# Mainboard.net
KiCad netlist of a schematic drawn in EAGLE
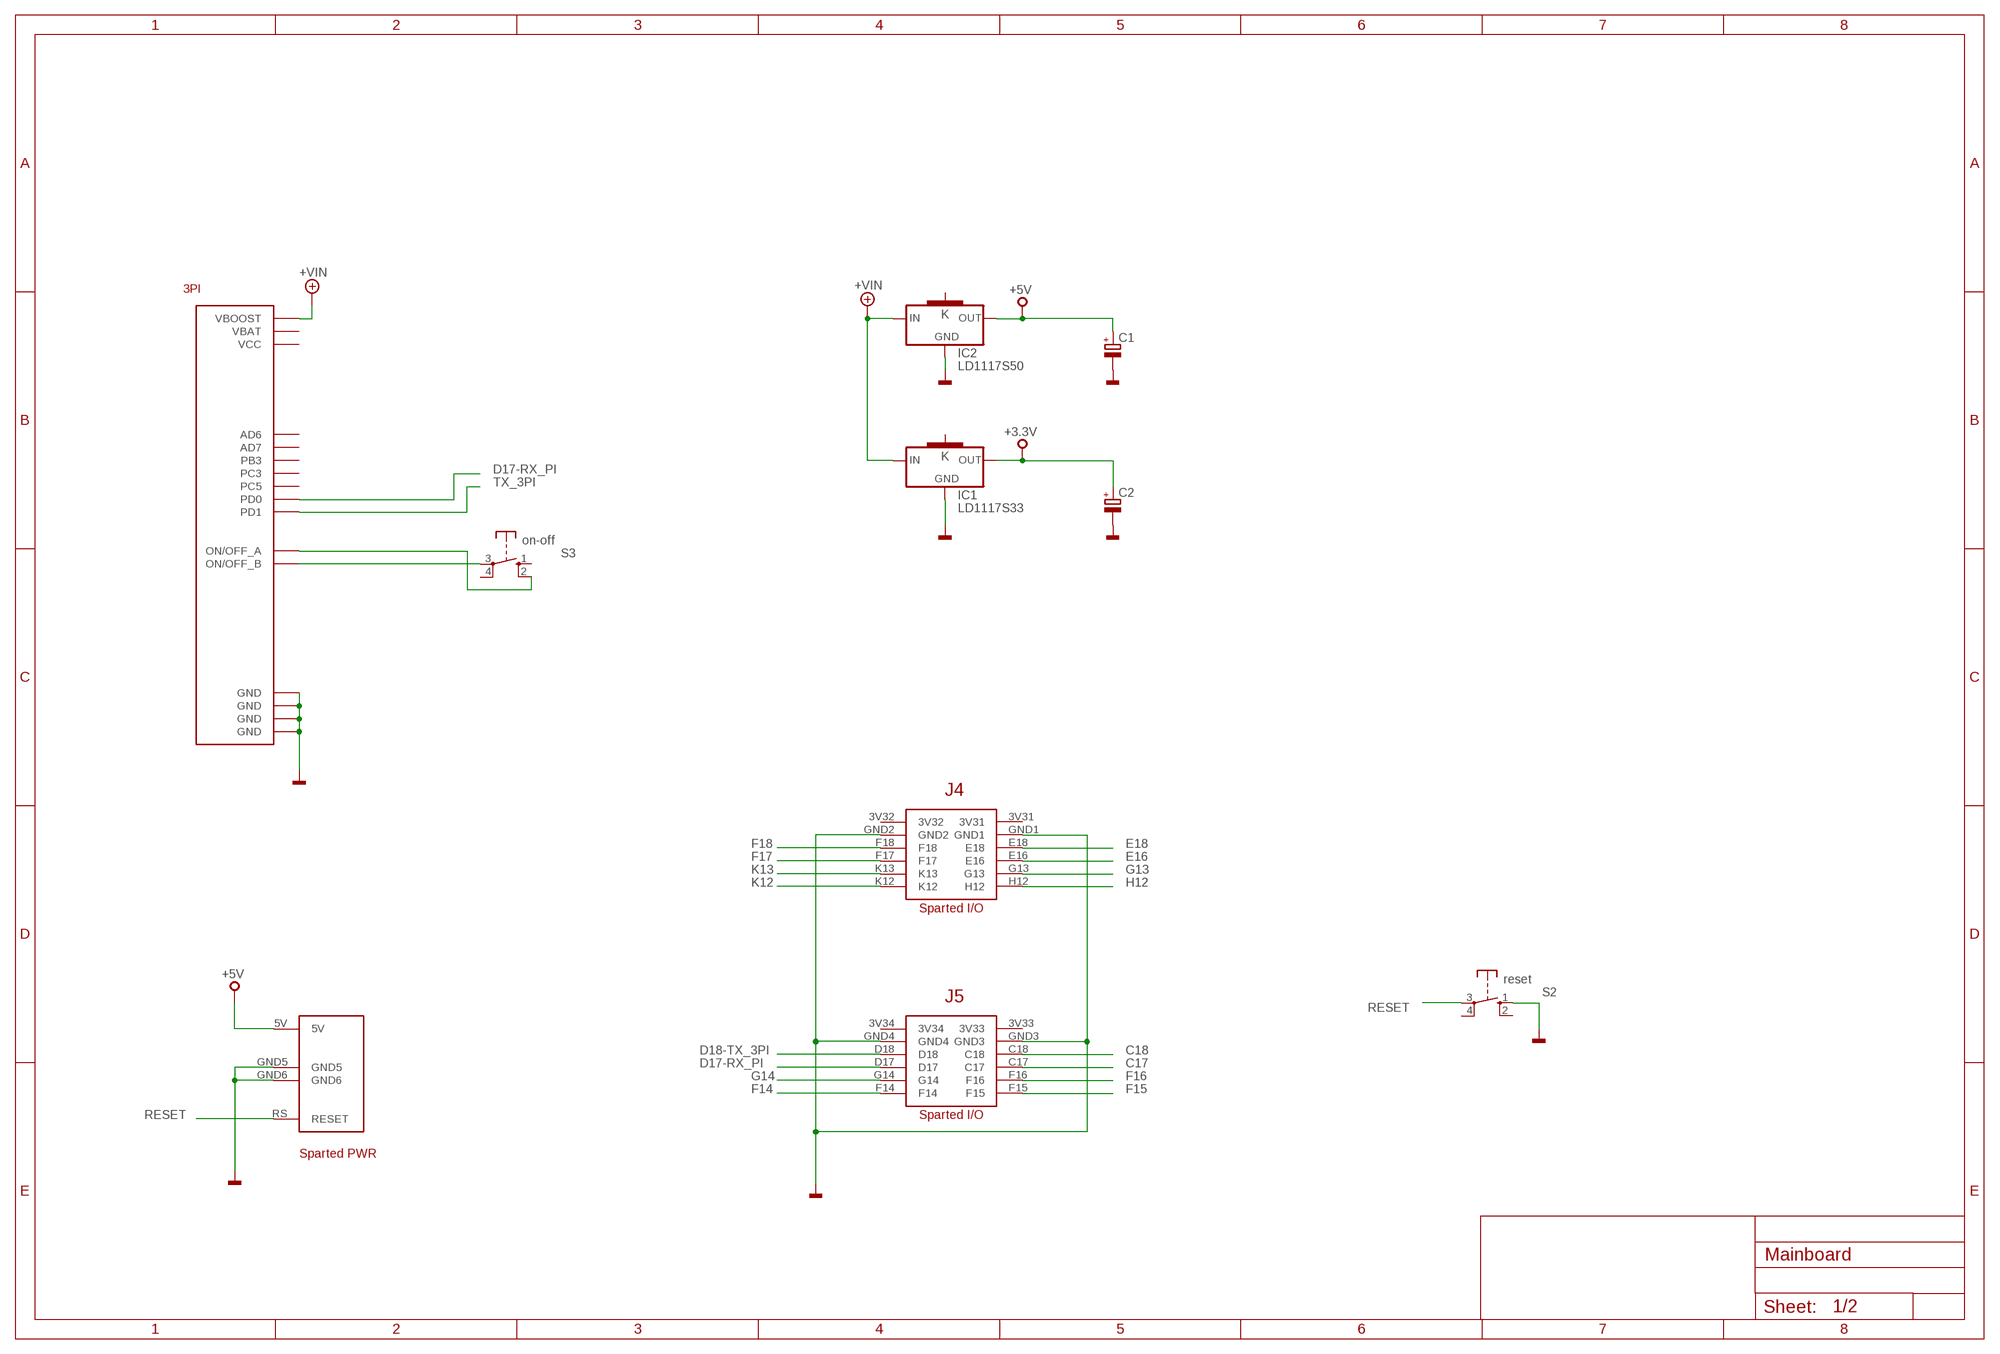
[diagram p0: schematic, sheet 1]
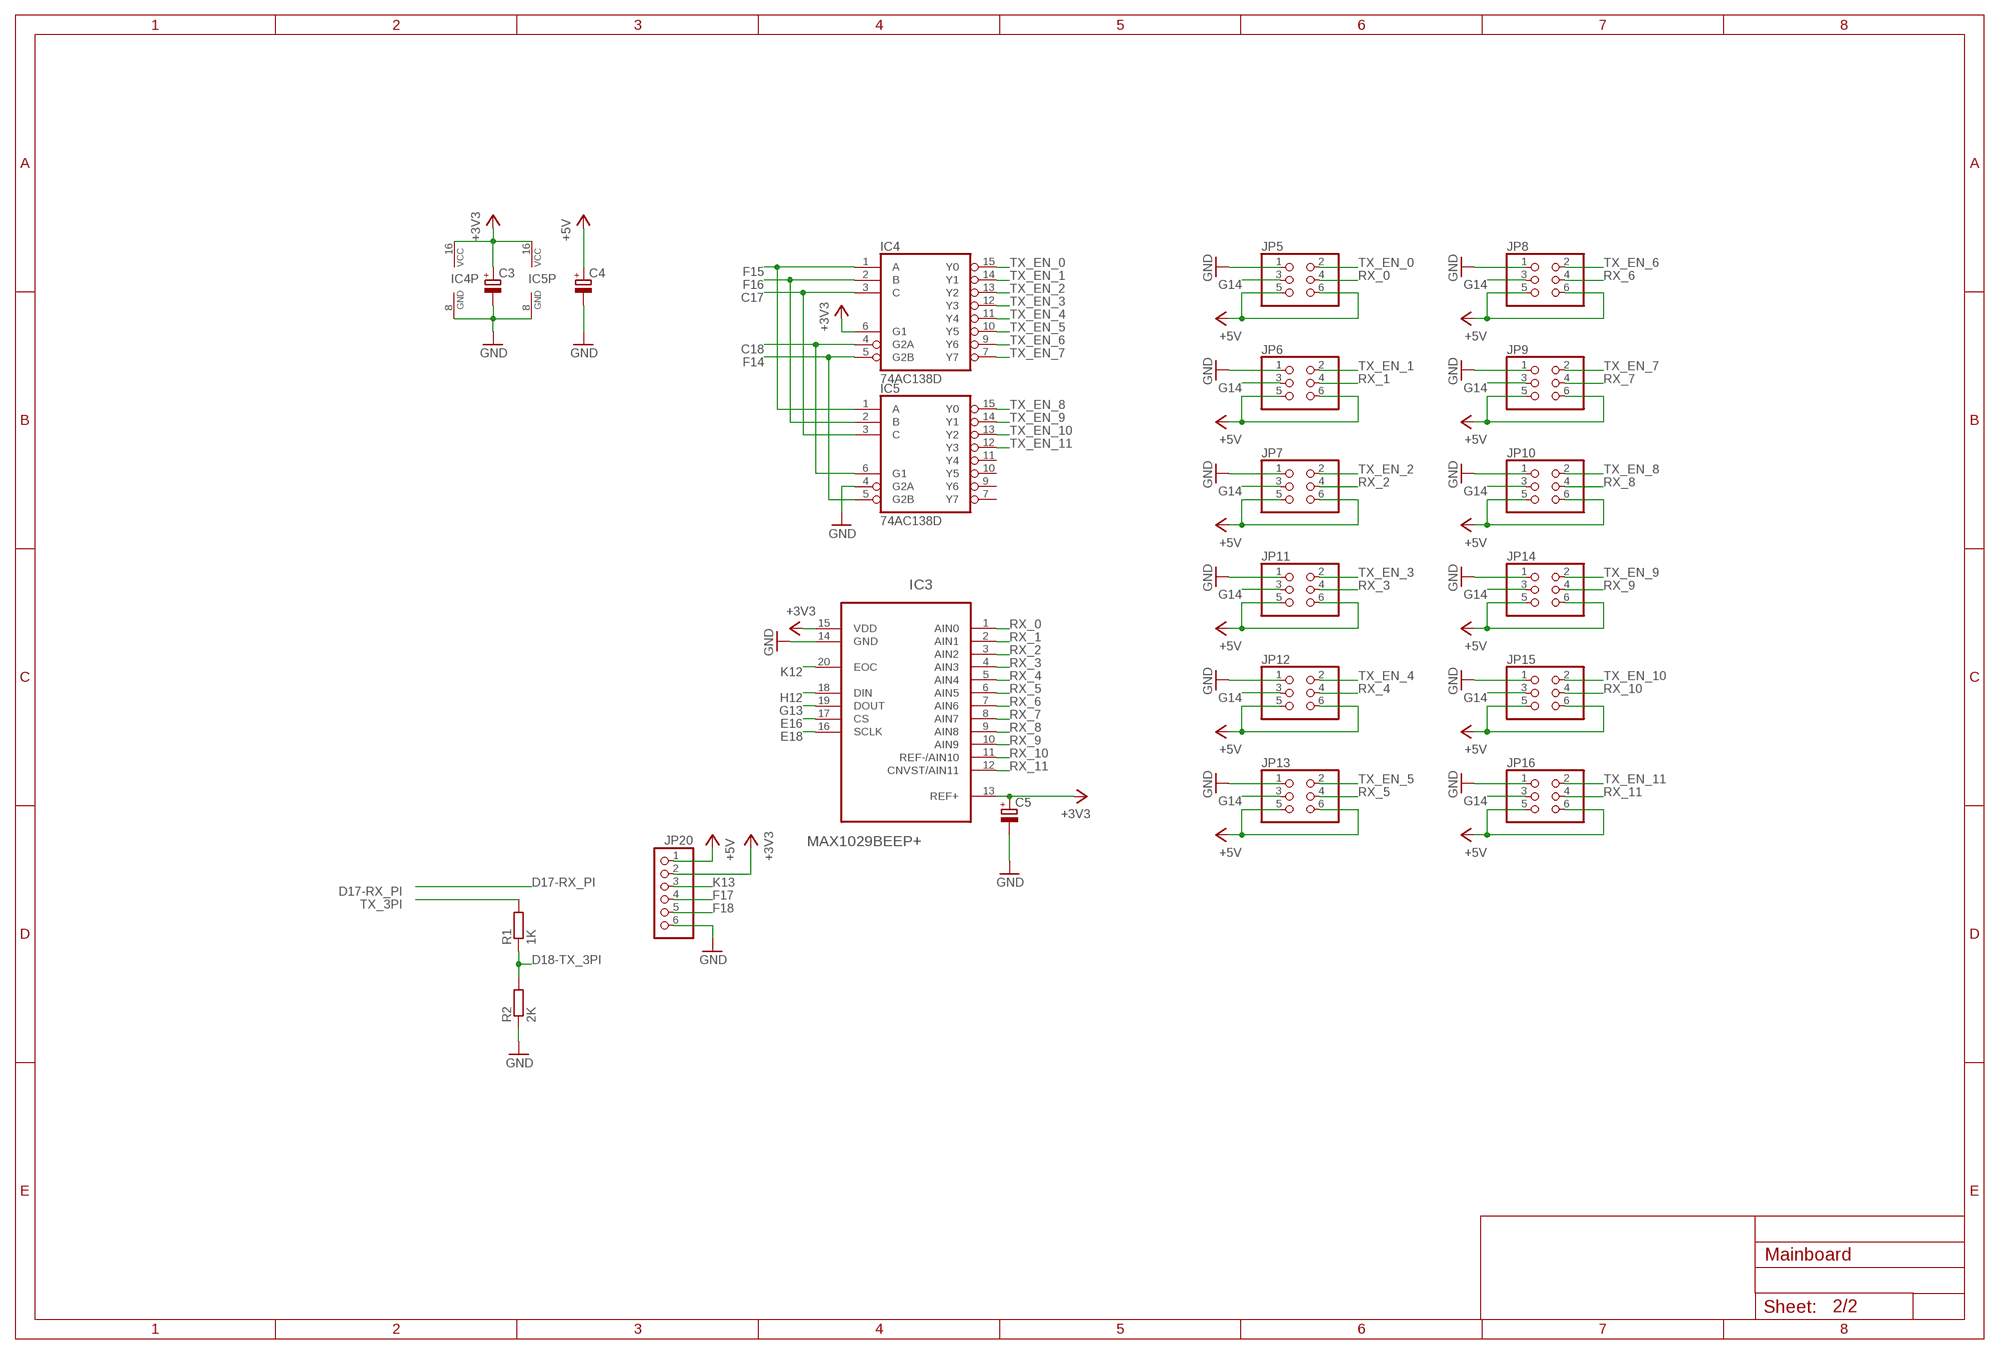
[diagram p1: schematic, sheet 2]

(export (version "E")
  (design (tool "Eeschema 10.0.6"))
  (components
    (comp (ref "C1")
      (value "CPOL-EUE2.5-5")
      (footprint "eagle-import:E2,5-5")
      (libsource (lib "eagle-import") (part "CPOL-EUE2.5-5"))
    )
    (comp (ref "C2")
      (value "CPOL-EUE2.5-5")
      (footprint "eagle-import:E2,5-5")
      (libsource (lib "eagle-import") (part "CPOL-EUE2.5-5"))
    )
    (comp (ref "IC1")
      (value "LD1117S33")
      (footprint "eagle-import:SOT223")
      (libsource (lib "eagle-import") (part "LD1117S33"))
    )
    (comp (ref "IC2")
      (value "LD1117S50")
      (footprint "eagle-import:SOT223")
      (libsource (lib "eagle-import") (part "LD1117S50"))
    )
    (comp (ref "S2")
      (value "reset")
      (footprint "eagle-import:DT6")
      (libsource (lib "eagle-import") (part "DT6"))
    )
    (comp (ref "S3")
      (value "on-off")
      (footprint "eagle-import:DT6")
      (libsource (lib "eagle-import") (part "DT6"))
    )
    (comp (ref "U$1")
      (value "M3PI-NO-LCD")
      (footprint "eagle-import:M3PI-NO-LCD")
      (libsource (lib "eagle-import") (part "M3PI-NO-LCD"))
    )
    (comp (ref "U$4")
      (value "LX9")
      (footprint "eagle-import:LX9")
      (libsource (lib "eagle-import") (part "LX9"))
    )
    (comp (ref "C3")
      (value "CPOL-EUE2-5")
      (footprint "eagle-import:E2-5")
      (libsource (lib "eagle-import") (part "CPOL-EUE2-5"))
    )
    (comp (ref "C4")
      (value "CPOL-EUE2-5")
      (footprint "eagle-import:E2-5")
      (libsource (lib "eagle-import") (part "CPOL-EUE2-5"))
    )
    (comp (ref "C5")
      (value "CPOL-EUE2-5")
      (footprint "eagle-import:E2-5")
      (libsource (lib "eagle-import") (part "CPOL-EUE2-5"))
    )
    (comp (ref "IC3")
      (value "MAX1029BEEP+")
      (footprint "eagle-import:SOP64P600X165-20N")
      (libsource (lib "eagle-import") (part "MAX1029BEEP+"))
    )
    (comp (ref "IC4")
      (value "74AC138D")
      (footprint "eagle-import:SO16")
      (fields (field (name "OC_FARNELL") "1201320"))
      (libsource (lib "eagle-import") (part "74138DAC"))
    )
    (comp (ref "IC5")
      (value "74AC138D")
      (footprint "eagle-import:SO16")
      (fields (field (name "OC_FARNELL") "1201320"))
      (libsource (lib "eagle-import") (part "74138DAC"))
    )
    (comp (ref "JP5")
      (value "PINHD-2X3")
      (footprint "eagle-import:2X03")
      (libsource (lib "eagle-import") (part "PINHD-2X3"))
    )
    (comp (ref "JP6")
      (value "PINHD-2X3/90")
      (footprint "eagle-import:2X03_90")
      (libsource (lib "eagle-import") (part "PINHD-2X3/90"))
    )
    (comp (ref "JP7")
      (value "PINHD-2X3/90")
      (footprint "eagle-import:2X03_90")
      (libsource (lib "eagle-import") (part "PINHD-2X3/90"))
    )
    (comp (ref "JP8")
      (value "PINHD-2X3/90")
      (footprint "eagle-import:2X03_90")
      (libsource (lib "eagle-import") (part "PINHD-2X3/90"))
    )
    (comp (ref "JP9")
      (value "PINHD-2X3")
      (footprint "eagle-import:2X03")
      (libsource (lib "eagle-import") (part "PINHD-2X3"))
    )
    (comp (ref "JP10")
      (value "PINHD-2X3/90")
      (footprint "eagle-import:2X03_90")
      (libsource (lib "eagle-import") (part "PINHD-2X3/90"))
    )
    (comp (ref "JP11")
      (value "PINHD-2X3/90")
      (footprint "eagle-import:2X03_90")
      (libsource (lib "eagle-import") (part "PINHD-2X3/90"))
    )
    (comp (ref "JP12")
      (value "PINHD-2X3/90")
      (footprint "eagle-import:2X03_90")
      (libsource (lib "eagle-import") (part "PINHD-2X3/90"))
    )
    (comp (ref "JP13")
      (value "PINHD-2X3/90")
      (footprint "eagle-import:2X03_90")
      (libsource (lib "eagle-import") (part "PINHD-2X3/90"))
    )
    (comp (ref "JP14")
      (value "PINHD-2X3/90")
      (footprint "eagle-import:2X03_90")
      (libsource (lib "eagle-import") (part "PINHD-2X3/90"))
    )
    (comp (ref "JP15")
      (value "PINHD-2X3/90")
      (footprint "eagle-import:2X03_90")
      (libsource (lib "eagle-import") (part "PINHD-2X3/90"))
    )
    (comp (ref "JP16")
      (value "PINHD-2X3/90")
      (footprint "eagle-import:2X03_90")
      (libsource (lib "eagle-import") (part "PINHD-2X3/90"))
    )
    (comp (ref "JP20")
      (value "PINHD-1X6")
      (footprint "eagle-import:1X06")
      (libsource (lib "eagle-import") (part "PINHD-1X6"))
    )
    (comp (ref "R1")
      (value "1K")
      (footprint "eagle-import:R0805")
      (libsource (lib "eagle-import") (part "R-EU_R0805"))
    )
    (comp (ref "R2")
      (value "2K")
      (footprint "eagle-import:R0805")
      (libsource (lib "eagle-import") (part "R-EU_R0805"))
    )
  )
  (nets
    (net (code "1") (name "+3.3V") (class "Default")
      (node (ref "C2") (pin "+") (pinfunction "+_+") (pintype "passive"))
      (node (ref "IC1") (pin "2") (pinfunction "OUT_2") (pintype "passive"))
    )
    (net (code "2") (name "+3V3") (class "Default")
      (node (ref "C3") (pin "+") (pinfunction "+_+") (pintype "passive"))
      (node (ref "C5") (pin "+") (pinfunction "+_+") (pintype "passive"))
      (node (ref "IC3") (pin "13") (pinfunction "REF+_13") (pintype "input"))
      (node (ref "IC3") (pin "15") (pinfunction "VDD_15") (pintype "power_in"))
      (node (ref "IC4") (pin "16") (pinfunction "VCC_16") (pintype "power_in"))
      (node (ref "IC4") (pin "6") (pinfunction "G1_6") (pintype "input"))
      (node (ref "IC5") (pin "16") (pinfunction "VCC_16") (pintype "power_in"))
      (node (ref "JP20") (pin "2") (pinfunction "2_2") (pintype "passive"))
    )
    (net (code "3") (name "+5V") (class "Default")
      (node (ref "C1") (pin "+") (pinfunction "+_+") (pintype "passive"))
      (node (ref "C4") (pin "+") (pinfunction "+_+") (pintype "passive"))
      (node (ref "IC2") (pin "2") (pinfunction "OUT_2") (pintype "passive"))
      (node (ref "JP10") (pin "5") (pinfunction "5_5") (pintype "passive"))
      (node (ref "JP10") (pin "6") (pinfunction "6_6") (pintype "passive"))
      (node (ref "JP11") (pin "5") (pinfunction "5_5") (pintype "passive"))
      (node (ref "JP11") (pin "6") (pinfunction "6_6") (pintype "passive"))
      (node (ref "JP12") (pin "5") (pinfunction "5_5") (pintype "passive"))
      (node (ref "JP12") (pin "6") (pinfunction "6_6") (pintype "passive"))
      (node (ref "JP13") (pin "5") (pinfunction "5_5") (pintype "passive"))
      (node (ref "JP13") (pin "6") (pinfunction "6_6") (pintype "passive"))
      (node (ref "JP14") (pin "5") (pinfunction "5_5") (pintype "passive"))
      (node (ref "JP14") (pin "6") (pinfunction "6_6") (pintype "passive"))
      (node (ref "JP15") (pin "5") (pinfunction "5_5") (pintype "passive"))
      (node (ref "JP15") (pin "6") (pinfunction "6_6") (pintype "passive"))
      (node (ref "JP16") (pin "5") (pinfunction "5_5") (pintype "passive"))
      (node (ref "JP16") (pin "6") (pinfunction "6_6") (pintype "passive"))
      (node (ref "JP20") (pin "1") (pinfunction "1_1") (pintype "passive"))
      (node (ref "JP5") (pin "5") (pinfunction "5_5") (pintype "passive"))
      (node (ref "JP5") (pin "6") (pinfunction "6_6") (pintype "passive"))
      (node (ref "JP6") (pin "5") (pinfunction "5_5") (pintype "passive"))
      (node (ref "JP6") (pin "6") (pinfunction "6_6") (pintype "passive"))
      (node (ref "JP7") (pin "5") (pinfunction "5_5") (pintype "passive"))
      (node (ref "JP7") (pin "6") (pinfunction "6_6") (pintype "passive"))
      (node (ref "JP8") (pin "5") (pinfunction "5_5") (pintype "passive"))
      (node (ref "JP8") (pin "6") (pinfunction "6_6") (pintype "passive"))
      (node (ref "JP9") (pin "5") (pinfunction "5_5") (pintype "passive"))
      (node (ref "JP9") (pin "6") (pinfunction "6_6") (pintype "passive"))
      (node (ref "U$4") (pin "5V") (pinfunction "5V_5V") (pintype "bidirectional"))
    )
    (net (code "4") (name "+VIN") (class "Default")
      (node (ref "IC1") (pin "3") (pinfunction "IN_3") (pintype "input"))
      (node (ref "IC2") (pin "3") (pinfunction "IN_3") (pintype "input"))
      (node (ref "U$1") (pin "VBOOST") (pinfunction "VBOOST_VBOOST") (pintype "bidirectional"))
    )
    (net (code "5") (name "C17") (class "Default")
      (node (ref "IC4") (pin "3") (pinfunction "C_3") (pintype "input"))
      (node (ref "IC5") (pin "3") (pinfunction "C_3") (pintype "input"))
      (node (ref "U$4") (pin "C17") (pinfunction "C17_C17") (pintype "bidirectional"))
    )
    (net (code "6") (name "C18") (class "Default")
      (node (ref "IC4") (pin "4") (pinfunction "G2A_4") (pintype "input"))
      (node (ref "IC5") (pin "6") (pinfunction "G1_6") (pintype "input"))
      (node (ref "U$4") (pin "C18") (pinfunction "C18_C18") (pintype "bidirectional"))
    )
    (net (code "7") (name "D17-RX_PI") (class "Default")
      (node (ref "U$1") (pin "PD0") (pinfunction "PD0_PD0") (pintype "bidirectional"))
      (node (ref "U$4") (pin "D17") (pinfunction "D17_D17") (pintype "bidirectional"))
    )
    (net (code "8") (name "D18-TX_3PI") (class "Default")
      (node (ref "R1") (pin "1") (pinfunction "1_1") (pintype "passive"))
      (node (ref "R2") (pin "2") (pinfunction "2_2") (pintype "passive"))
      (node (ref "U$4") (pin "D18") (pinfunction "D18_D18") (pintype "bidirectional"))
    )
    (net (code "9") (name "E16") (class "Default")
      (node (ref "IC3") (pin "17") (pinfunction "CS_17") (pintype "input"))
      (node (ref "U$4") (pin "E16") (pinfunction "E16_E16") (pintype "bidirectional"))
    )
    (net (code "10") (name "E18") (class "Default")
      (node (ref "IC3") (pin "16") (pinfunction "SCLK_16") (pintype "input"))
      (node (ref "U$4") (pin "E18") (pinfunction "E18_E18") (pintype "bidirectional"))
    )
    (net (code "11") (name "F14") (class "Default")
      (node (ref "IC4") (pin "5") (pinfunction "G2B_5") (pintype "input"))
      (node (ref "IC5") (pin "5") (pinfunction "G2B_5") (pintype "input"))
      (node (ref "U$4") (pin "F14") (pinfunction "F14_F14") (pintype "bidirectional"))
    )
    (net (code "12") (name "F15") (class "Default")
      (node (ref "IC4") (pin "1") (pinfunction "A_1") (pintype "input"))
      (node (ref "IC5") (pin "1") (pinfunction "A_1") (pintype "input"))
      (node (ref "U$4") (pin "F15") (pinfunction "F15_F15") (pintype "bidirectional"))
    )
    (net (code "13") (name "F16") (class "Default")
      (node (ref "IC4") (pin "2") (pinfunction "B_2") (pintype "input"))
      (node (ref "IC5") (pin "2") (pinfunction "B_2") (pintype "input"))
      (node (ref "U$4") (pin "F16") (pinfunction "F16_F16") (pintype "bidirectional"))
    )
    (net (code "14") (name "F17") (class "Default")
      (node (ref "JP20") (pin "4") (pinfunction "4_4") (pintype "passive"))
      (node (ref "U$4") (pin "F17") (pinfunction "F17_F17") (pintype "bidirectional"))
    )
    (net (code "15") (name "F18") (class "Default")
      (node (ref "JP20") (pin "5") (pinfunction "5_5") (pintype "passive"))
      (node (ref "U$4") (pin "F18") (pinfunction "F18_F18") (pintype "bidirectional"))
    )
    (net (code "16") (name "G13") (class "Default")
      (node (ref "IC3") (pin "19") (pinfunction "DOUT_19") (pintype "output"))
      (node (ref "U$4") (pin "G13") (pinfunction "G13_G13") (pintype "bidirectional"))
    )
    (net (code "17") (name "G14") (class "Default")
      (node (ref "JP10") (pin "3") (pinfunction "3_3") (pintype "passive"))
      (node (ref "JP11") (pin "3") (pinfunction "3_3") (pintype "passive"))
      (node (ref "JP12") (pin "3") (pinfunction "3_3") (pintype "passive"))
      (node (ref "JP13") (pin "3") (pinfunction "3_3") (pintype "passive"))
      (node (ref "JP14") (pin "3") (pinfunction "3_3") (pintype "passive"))
      (node (ref "JP15") (pin "3") (pinfunction "3_3") (pintype "passive"))
      (node (ref "JP16") (pin "3") (pinfunction "3_3") (pintype "passive"))
      (node (ref "JP5") (pin "3") (pinfunction "3_3") (pintype "passive"))
      (node (ref "JP6") (pin "3") (pinfunction "3_3") (pintype "passive"))
      (node (ref "JP7") (pin "3") (pinfunction "3_3") (pintype "passive"))
      (node (ref "JP8") (pin "3") (pinfunction "3_3") (pintype "passive"))
      (node (ref "JP9") (pin "3") (pinfunction "3_3") (pintype "passive"))
      (node (ref "U$4") (pin "G14") (pinfunction "G14_G14") (pintype "bidirectional"))
    )
    (net (code "18") (name "GND") (class "Default")
      (node (ref "C1") (pin "-") (pinfunction "-_-") (pintype "passive"))
      (node (ref "C2") (pin "-") (pinfunction "-_-") (pintype "passive"))
      (node (ref "C3") (pin "-") (pinfunction "-_-") (pintype "passive"))
      (node (ref "C4") (pin "-") (pinfunction "-_-") (pintype "passive"))
      (node (ref "C5") (pin "-") (pinfunction "-_-") (pintype "passive"))
      (node (ref "IC1") (pin "1") (pinfunction "GND_1") (pintype "input"))
      (node (ref "IC2") (pin "1") (pinfunction "GND_1") (pintype "input"))
      (node (ref "IC3") (pin "14") (pinfunction "GND_14") (pintype "power_in"))
      (node (ref "IC4") (pin "8") (pinfunction "GND_8") (pintype "power_in"))
      (node (ref "IC5") (pin "4") (pinfunction "G2A_4") (pintype "input"))
      (node (ref "IC5") (pin "8") (pinfunction "GND_8") (pintype "power_in"))
      (node (ref "JP10") (pin "1") (pinfunction "1_1") (pintype "passive"))
      (node (ref "JP11") (pin "1") (pinfunction "1_1") (pintype "passive"))
      (node (ref "JP12") (pin "1") (pinfunction "1_1") (pintype "passive"))
      (node (ref "JP13") (pin "1") (pinfunction "1_1") (pintype "passive"))
      (node (ref "JP14") (pin "1") (pinfunction "1_1") (pintype "passive"))
      (node (ref "JP15") (pin "1") (pinfunction "1_1") (pintype "passive"))
      (node (ref "JP16") (pin "1") (pinfunction "1_1") (pintype "passive"))
      (node (ref "JP20") (pin "6") (pinfunction "6_6") (pintype "passive"))
      (node (ref "JP5") (pin "1") (pinfunction "1_1") (pintype "passive"))
      (node (ref "JP6") (pin "1") (pinfunction "1_1") (pintype "passive"))
      (node (ref "JP7") (pin "1") (pinfunction "1_1") (pintype "passive"))
      (node (ref "JP8") (pin "1") (pinfunction "1_1") (pintype "passive"))
      (node (ref "JP9") (pin "1") (pinfunction "1_1") (pintype "passive"))
      (node (ref "R2") (pin "1") (pinfunction "1_1") (pintype "passive"))
      (node (ref "S2") (pin "1") (pinfunction "S_1") (pintype "passive"))
      (node (ref "U$1") (pin "GND@1") (pinfunction "GND_GND@1") (pintype "bidirectional"))
      (node (ref "U$1") (pin "GND@2") (pinfunction "GND_GND@2") (pintype "bidirectional"))
      (node (ref "U$1") (pin "GND@3") (pinfunction "GND_GND@3") (pintype "bidirectional"))
      (node (ref "U$1") (pin "GND@4") (pinfunction "GND_GND@4") (pintype "bidirectional"))
      (node (ref "U$4") (pin "GND1") (pinfunction "GND1_GND1") (pintype "bidirectional"))
      (node (ref "U$4") (pin "GND2") (pinfunction "GND2_GND2") (pintype "bidirectional"))
      (node (ref "U$4") (pin "GND3") (pinfunction "GND3_GND3") (pintype "bidirectional"))
      (node (ref "U$4") (pin "GND4") (pinfunction "GND4_GND4") (pintype "bidirectional"))
      (node (ref "U$4") (pin "GND5") (pinfunction "GND5_GND5") (pintype "bidirectional"))
      (node (ref "U$4") (pin "GND6") (pinfunction "GND6_GND6") (pintype "bidirectional"))
    )
    (net (code "19") (name "H12") (class "Default")
      (node (ref "IC3") (pin "18") (pinfunction "DIN_18") (pintype "input"))
      (node (ref "U$4") (pin "H12") (pinfunction "H12_H12") (pintype "bidirectional"))
    )
    (net (code "20") (name "K12") (class "Default")
      (node (ref "IC3") (pin "20") (pinfunction "EOC_20") (pintype "output"))
      (node (ref "U$4") (pin "K12") (pinfunction "K12_K12") (pintype "bidirectional"))
    )
    (net (code "21") (name "K13") (class "Default")
      (node (ref "JP20") (pin "3") (pinfunction "3_3") (pintype "passive"))
      (node (ref "U$4") (pin "K13") (pinfunction "K13_K13") (pintype "bidirectional"))
    )
    (net (code "22") (name "Net-(S3-P-Pad3)") (class "Default")
      (node (ref "S3") (pin "3") (pinfunction "P_3") (pintype "passive"))
      (node (ref "U$1") (pin "ON/OFF_B") (pinfunction "ON/OFF_B_ON/OFF_B") (pintype "bidirectional"))
    )
    (net (code "23") (name "Net-(S3-S-Pad2)") (class "Default")
      (node (ref "S3") (pin "2") (pinfunction "S_2") (pintype "passive"))
      (node (ref "U$1") (pin "ON/OFF_A") (pinfunction "ON/OFF_A_ON/OFF_A") (pintype "bidirectional"))
    )
    (net (code "24") (name "RESET") (class "Default")
      (node (ref "S2") (pin "3") (pinfunction "P_3") (pintype "passive"))
      (node (ref "U$4") (pin "RS") (pinfunction "RESET_RS") (pintype "bidirectional"))
    )
    (net (code "25") (name "RX_0") (class "Default")
      (node (ref "IC3") (pin "1") (pinfunction "AIN0_1") (pintype "input"))
      (node (ref "JP5") (pin "4") (pinfunction "4_4") (pintype "passive"))
    )
    (net (code "26") (name "RX_1") (class "Default")
      (node (ref "IC3") (pin "2") (pinfunction "AIN1_2") (pintype "input"))
      (node (ref "JP6") (pin "4") (pinfunction "4_4") (pintype "passive"))
    )
    (net (code "27") (name "RX_2") (class "Default")
      (node (ref "IC3") (pin "3") (pinfunction "AIN2_3") (pintype "input"))
      (node (ref "JP7") (pin "4") (pinfunction "4_4") (pintype "passive"))
    )
    (net (code "28") (name "RX_3") (class "Default")
      (node (ref "IC3") (pin "4") (pinfunction "AIN3_4") (pintype "input"))
      (node (ref "JP11") (pin "4") (pinfunction "4_4") (pintype "passive"))
    )
    (net (code "29") (name "RX_4") (class "Default")
      (node (ref "IC3") (pin "5") (pinfunction "AIN4_5") (pintype "input"))
      (node (ref "JP12") (pin "4") (pinfunction "4_4") (pintype "passive"))
    )
    (net (code "30") (name "RX_5") (class "Default")
      (node (ref "IC3") (pin "6") (pinfunction "AIN5_6") (pintype "input"))
      (node (ref "JP13") (pin "4") (pinfunction "4_4") (pintype "passive"))
    )
    (net (code "31") (name "RX_6") (class "Default")
      (node (ref "IC3") (pin "7") (pinfunction "AIN6_7") (pintype "input"))
      (node (ref "JP8") (pin "4") (pinfunction "4_4") (pintype "passive"))
    )
    (net (code "32") (name "RX_7") (class "Default")
      (node (ref "IC3") (pin "8") (pinfunction "AIN7_8") (pintype "input"))
      (node (ref "JP9") (pin "4") (pinfunction "4_4") (pintype "passive"))
    )
    (net (code "33") (name "RX_8") (class "Default")
      (node (ref "IC3") (pin "9") (pinfunction "AIN8_9") (pintype "input"))
      (node (ref "JP10") (pin "4") (pinfunction "4_4") (pintype "passive"))
    )
    (net (code "34") (name "RX_9") (class "Default")
      (node (ref "IC3") (pin "10") (pinfunction "AIN9_10") (pintype "input"))
      (node (ref "JP14") (pin "4") (pinfunction "4_4") (pintype "passive"))
    )
    (net (code "35") (name "RX_10") (class "Default")
      (node (ref "IC3") (pin "11") (pinfunction "REF-/AIN10_11") (pintype "input"))
      (node (ref "JP15") (pin "4") (pinfunction "4_4") (pintype "passive"))
    )
    (net (code "36") (name "RX_11") (class "Default")
      (node (ref "IC3") (pin "12") (pinfunction "CNVST/AIN11_12") (pintype "input"))
      (node (ref "JP16") (pin "4") (pinfunction "4_4") (pintype "passive"))
    )
    (net (code "37") (name "TX_3PI") (class "Default")
      (node (ref "R1") (pin "2") (pinfunction "2_2") (pintype "passive"))
      (node (ref "U$1") (pin "PD1") (pinfunction "PD1_PD1") (pintype "bidirectional"))
    )
    (net (code "38") (name "TX_EN_0") (class "Default")
      (node (ref "IC4") (pin "15") (pinfunction "Y0_15") (pintype "output"))
      (node (ref "JP5") (pin "2") (pinfunction "2_2") (pintype "passive"))
    )
    (net (code "39") (name "TX_EN_1") (class "Default")
      (node (ref "IC4") (pin "14") (pinfunction "Y1_14") (pintype "output"))
      (node (ref "JP6") (pin "2") (pinfunction "2_2") (pintype "passive"))
    )
    (net (code "40") (name "TX_EN_2") (class "Default")
      (node (ref "IC4") (pin "13") (pinfunction "Y2_13") (pintype "output"))
      (node (ref "JP7") (pin "2") (pinfunction "2_2") (pintype "passive"))
    )
    (net (code "41") (name "TX_EN_3") (class "Default")
      (node (ref "IC4") (pin "12") (pinfunction "Y3_12") (pintype "output"))
      (node (ref "JP11") (pin "2") (pinfunction "2_2") (pintype "passive"))
    )
    (net (code "42") (name "TX_EN_4") (class "Default")
      (node (ref "IC4") (pin "11") (pinfunction "Y4_11") (pintype "output"))
      (node (ref "JP12") (pin "2") (pinfunction "2_2") (pintype "passive"))
    )
    (net (code "43") (name "TX_EN_5") (class "Default")
      (node (ref "IC4") (pin "10") (pinfunction "Y5_10") (pintype "output"))
      (node (ref "JP13") (pin "2") (pinfunction "2_2") (pintype "passive"))
    )
    (net (code "44") (name "TX_EN_6") (class "Default")
      (node (ref "IC4") (pin "9") (pinfunction "Y6_9") (pintype "output"))
      (node (ref "JP8") (pin "2") (pinfunction "2_2") (pintype "passive"))
    )
    (net (code "45") (name "TX_EN_7") (class "Default")
      (node (ref "IC4") (pin "7") (pinfunction "Y7_7") (pintype "output"))
      (node (ref "JP9") (pin "2") (pinfunction "2_2") (pintype "passive"))
    )
    (net (code "46") (name "TX_EN_8") (class "Default")
      (node (ref "IC5") (pin "15") (pinfunction "Y0_15") (pintype "output"))
      (node (ref "JP10") (pin "2") (pinfunction "2_2") (pintype "passive"))
    )
    (net (code "47") (name "TX_EN_9") (class "Default")
      (node (ref "IC5") (pin "14") (pinfunction "Y1_14") (pintype "output"))
      (node (ref "JP14") (pin "2") (pinfunction "2_2") (pintype "passive"))
    )
    (net (code "48") (name "TX_EN_10") (class "Default")
      (node (ref "IC5") (pin "13") (pinfunction "Y2_13") (pintype "output"))
      (node (ref "JP15") (pin "2") (pinfunction "2_2") (pintype "passive"))
    )
    (net (code "49") (name "TX_EN_11") (class "Default")
      (node (ref "IC5") (pin "12") (pinfunction "Y3_12") (pintype "output"))
      (node (ref "JP16") (pin "2") (pinfunction "2_2") (pintype "passive"))
    )
    (net (code "50") (name "unconnected-(IC1-K-Pad4)") (class "Default")
      (node (ref "IC1") (pin "4") (pinfunction "K_4") (pintype "passive"))
    )
    (net (code "51") (name "unconnected-(IC2-K-Pad4)") (class "Default")
      (node (ref "IC2") (pin "4") (pinfunction "K_4") (pintype "passive"))
    )
    (net (code "52") (name "unconnected-(IC5A-Y4-Pad11)") (class "Default")
      (node (ref "IC5") (pin "11") (pinfunction "Y4_11") (pintype "output"))
    )
    (net (code "53") (name "unconnected-(IC5A-Y5-Pad10)") (class "Default")
      (node (ref "IC5") (pin "10") (pinfunction "Y5_10") (pintype "output"))
    )
    (net (code "54") (name "unconnected-(IC5A-Y6-Pad9)") (class "Default")
      (node (ref "IC5") (pin "9") (pinfunction "Y6_9") (pintype "output"))
    )
    (net (code "55") (name "unconnected-(IC5A-Y7-Pad7)") (class "Default")
      (node (ref "IC5") (pin "7") (pinfunction "Y7_7") (pintype "output"))
    )
    (net (code "56") (name "unconnected-(S2-P-Pad4)") (class "Default")
      (node (ref "S2") (pin "4") (pinfunction "P_4") (pintype "passive"))
    )
    (net (code "57") (name "unconnected-(S2-S-Pad2)") (class "Default")
      (node (ref "S2") (pin "2") (pinfunction "S_2") (pintype "passive"))
    )
    (net (code "58") (name "unconnected-(S3-P-Pad4)") (class "Default")
      (node (ref "S3") (pin "4") (pinfunction "P_4") (pintype "passive"))
    )
    (net (code "59") (name "unconnected-(S3-S-Pad1)") (class "Default")
      (node (ref "S3") (pin "1") (pinfunction "S_1") (pintype "passive"))
    )
    (net (code "60") (name "unconnected-(U$1-PadAD6)") (class "Default")
      (node (ref "U$1") (pin "AD6") (pinfunction "AD6_AD6") (pintype "bidirectional"))
    )
    (net (code "61") (name "unconnected-(U$1-PadAD7)") (class "Default")
      (node (ref "U$1") (pin "AD7") (pinfunction "AD7_AD7") (pintype "bidirectional"))
    )
    (net (code "62") (name "unconnected-(U$1-PadPB3)") (class "Default")
      (node (ref "U$1") (pin "PB3") (pinfunction "PB3_PB3") (pintype "bidirectional"))
    )
    (net (code "63") (name "unconnected-(U$1-PadPC3)") (class "Default")
      (node (ref "U$1") (pin "PC3") (pinfunction "PC3_PC3") (pintype "bidirectional"))
    )
    (net (code "64") (name "unconnected-(U$1-PadPC5)") (class "Default")
      (node (ref "U$1") (pin "PC5") (pinfunction "PC5_PC5") (pintype "bidirectional"))
    )
    (net (code "65") (name "unconnected-(U$1-PadVBAT)") (class "Default")
      (node (ref "U$1") (pin "VBAT") (pinfunction "VBAT_VBAT") (pintype "bidirectional"))
    )
    (net (code "66") (name "unconnected-(U$1-PadVCC)") (class "Default")
      (node (ref "U$1") (pin "VCC") (pinfunction "VCC_VCC") (pintype "bidirectional"))
    )
    (net (code "67") (name "unconnected-(U$4-Pad3V31)") (class "Default")
      (node (ref "U$4") (pin "3V31") (pinfunction "3V31_3V31") (pintype "bidirectional"))
    )
    (net (code "68") (name "unconnected-(U$4-Pad3V32)") (class "Default")
      (node (ref "U$4") (pin "3V32") (pinfunction "3V32_3V32") (pintype "bidirectional"))
    )
    (net (code "69") (name "unconnected-(U$4-Pad3V33)") (class "Default")
      (node (ref "U$4") (pin "3V33") (pinfunction "3V33_3V33") (pintype "bidirectional"))
    )
    (net (code "70") (name "unconnected-(U$4-Pad3V34)") (class "Default")
      (node (ref "U$4") (pin "3V34") (pinfunction "3V34_3V34") (pintype "bidirectional"))
    )
  )
)
